# muscle.net
KiCad netlist of a schematic drawn in EAGLE
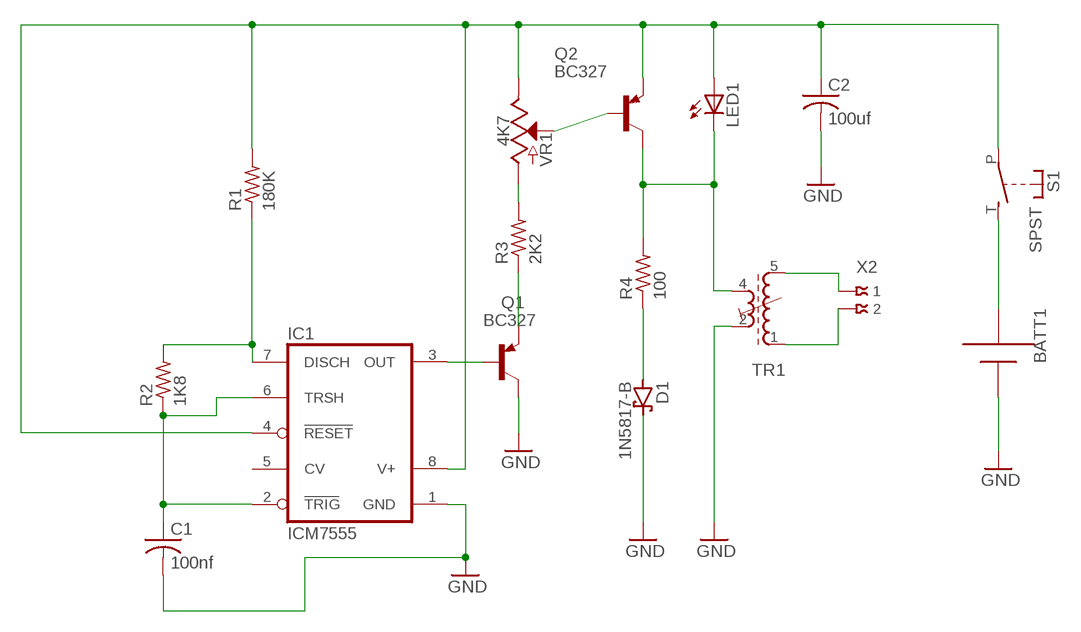
[diagram p0: schematic, sheet 1]

(export (version "E")
  (design (tool "Eeschema 10.0.6"))
  (components
    (comp (ref "BATT1")
      (value "AAA")
      (footprint "eagle-import:12BH412")
      (fields (field (name "MF") "BULGIN") (field (name "MPN") "BX0034"))
      (libsource (lib "eagle-import") (part "AAA"))
    )
    (comp (ref "C1")
      (value "100nf")
      (footprint "eagle-import:C025-024X044")
      (fields (field (name "MF") "AVX") (field (name "MPN") "12065C104KAT2A"))
      (libsource (lib "eagle-import") (part "C-US025-024X044"))
    )
    (comp (ref "C2")
      (value "100uf")
      (footprint "eagle-import:C025-024X044")
      (fields (field (name "MF") "KEMET") (field (name "MPN") "C1210C107M9PACTU"))
      (libsource (lib "eagle-import") (part "C-US025-024X044"))
    )
    (comp (ref "D1")
      (value "1N5817-B")
      (footprint "eagle-import:DO41-7.6")
      (fields (field (name "MF") "ON SEMICONDUCTOR") (field (name "MPN") "1N5817G"))
      (libsource (lib "eagle-import") (part "1N5817-B"))
    )
    (comp (ref "IC1")
      (value "ICM7555")
      (footprint "eagle-import:DIL08")
      (fields
        (field (name "MF") "MAXIM")
        (field (name "MPN") "ICM7555IPA+")
        (field (name "MF_1") "RENESAS")
        (field (name "MPN_1") "ICM7555IPAZ")
      )
      (libsource (lib "eagle-import") (part "ICM7555"))
    )
    (comp (ref "LED1")
      (value "LED3MM")
      (footprint "eagle-import:LED3MM")
      (fields (field (name "MF") "KINGBRIGHT") (field (name "MPN") "L-424IDT"))
      (libsource (lib "eagle-import") (part "LED3MM"))
    )
    (comp (ref "Q1")
      (value "BC327")
      (footprint "eagle-import:TO92")
      (libsource (lib "eagle-import") (part "BC327"))
    )
    (comp (ref "Q2")
      (value "BC327")
      (footprint "eagle-import:TO92")
      (libsource (lib "eagle-import") (part "BC327"))
    )
    (comp (ref "R1")
      (value "180K")
      (footprint "eagle-import:0204V")
      (libsource (lib "eagle-import") (part "R-US_0204/2V"))
    )
    (comp (ref "R2")
      (value "1K8")
      (footprint "eagle-import:0204V")
      (libsource (lib "eagle-import") (part "R-US_0204/2V"))
    )
    (comp (ref "R3")
      (value "2K2")
      (footprint "eagle-import:0204V")
      (libsource (lib "eagle-import") (part "R-US_0204/2V"))
    )
    (comp (ref "R4")
      (value "100")
      (footprint "eagle-import:0204V")
      (libsource (lib "eagle-import") (part "R-US_0204/2V"))
    )
    (comp (ref "S1")
      (value "SPST")
      (footprint "eagle-import:JUDCOSPST")
      (libsource (lib "eagle-import") (part "SPST"))
    )
    (comp (ref "TR1")
      (value "71-4-1524")
      (footprint "eagle-import:71-5")
      (libsource (lib "eagle-import") (part "71-4-1524"))
    )
    (comp (ref "VR1")
      (value "4K7")
      (footprint "eagle-import:SLIDER-SMALL")
      (libsource (lib "eagle-import") (part "POTENTIOMETER_SLIDE-20MM-1/10W-20%"))
    )
    (comp (ref "X2")
      (value "009177002")
      (footprint "eagle-import:009177002")
      (fields (field (name "MPN") "009177002001006"))
      (libsource (lib "eagle-import") (part "00917?0027"))
    )
  )
  (nets
    (net (code "1") (name "GND") (class "Default")
      (node (ref "BATT1") (pin "+") (pinfunction "+_+") (pintype "bidirectional"))
      (node (ref "C1") (pin "2") (pinfunction "2_2") (pintype "passive"))
      (node (ref "C2") (pin "2") (pinfunction "2_2") (pintype "passive"))
      (node (ref "D1") (pin "C") (pinfunction "C_C") (pintype "passive"))
      (node (ref "IC1") (pin "1") (pinfunction "GND_1") (pintype "power_in"))
      (node (ref "Q1") (pin "3") (pinfunction "C_3") (pintype "passive"))
      (node (ref "TR1") (pin "2") (pinfunction "A2_2") (pintype "passive"))
    )
    (net (code "2") (name "Net-(D1-PadA)") (class "Default")
      (node (ref "D1") (pin "A") (pinfunction "A_A") (pintype "passive"))
      (node (ref "R4") (pin "1") (pinfunction "1_1") (pintype "passive"))
    )
    (net (code "3") (name "Net-(IC1-DISCH)") (class "Default")
      (node (ref "IC1") (pin "7") (pinfunction "DISCH_7") (pintype "input"))
      (node (ref "R1") (pin "1") (pinfunction "1_1") (pintype "passive"))
      (node (ref "R2") (pin "2") (pinfunction "2_2") (pintype "passive"))
    )
    (net (code "4") (name "Net-(IC1-OUT)") (class "Default")
      (node (ref "IC1") (pin "3") (pinfunction "OUT_3") (pintype "output"))
      (node (ref "Q1") (pin "2") (pinfunction "B_2") (pintype "passive"))
    )
    (net (code "5") (name "Net-(IC1-RESET)") (class "Default")
      (node (ref "C2") (pin "1") (pinfunction "1_1") (pintype "passive"))
      (node (ref "IC1") (pin "4") (pinfunction "RESET_4") (pintype "input"))
      (node (ref "IC1") (pin "8") (pinfunction "V+_8") (pintype "power_in"))
      (node (ref "LED1") (pin "A") (pinfunction "A_A") (pintype "passive"))
      (node (ref "Q2") (pin "1") (pinfunction "E_1") (pintype "passive"))
      (node (ref "R1") (pin "2") (pinfunction "2_2") (pintype "passive"))
      (node (ref "S1") (pin "P") (pinfunction "P_P") (pintype "passive"))
      (node (ref "VR1") (pin "TOP") (pinfunction "E_TOP") (pintype "passive"))
    )
    (net (code "6") (name "Net-(IC1-TRIG)") (class "Default")
      (node (ref "C1") (pin "1") (pinfunction "1_1") (pintype "passive"))
      (node (ref "IC1") (pin "2") (pinfunction "TRIG_2") (pintype "bidirectional"))
      (node (ref "IC1") (pin "6") (pinfunction "TRSH_6") (pintype "input"))
      (node (ref "R2") (pin "1") (pinfunction "1_1") (pintype "passive"))
    )
    (net (code "7") (name "Net-(LED1-C)") (class "Default")
      (node (ref "LED1") (pin "K") (pinfunction "C_K") (pintype "passive"))
      (node (ref "Q2") (pin "3") (pinfunction "C_3") (pintype "passive"))
      (node (ref "R4") (pin "2") (pinfunction "2_2") (pintype "passive"))
      (node (ref "TR1") (pin "4") (pinfunction "E2_4") (pintype "passive"))
    )
    (net (code "8") (name "Net-(Q1-E)") (class "Default")
      (node (ref "Q1") (pin "1") (pinfunction "E_1") (pintype "passive"))
      (node (ref "R3") (pin "1") (pinfunction "1_1") (pintype "passive"))
    )
    (net (code "9") (name "Net-(Q2-B)") (class "Default")
      (node (ref "Q2") (pin "2") (pinfunction "B_2") (pintype "passive"))
      (node (ref "VR1") (pin "WIPER") (pinfunction "S_WIPER") (pintype "passive"))
    )
    (net (code "10") (name "Net-(S1-S)") (class "Default")
      (node (ref "BATT1") (pin "-") (pinfunction "-_-") (pintype "bidirectional"))
      (node (ref "S1") (pin "T") (pinfunction "S_T") (pintype "passive"))
    )
    (net (code "11") (name "Net-(TR1A-A1)") (class "Default")
      (node (ref "TR1") (pin "1") (pinfunction "A1_1") (pintype "passive"))
      (node (ref "X2") (pin "2") (pinfunction "2_2") (pintype "passive"))
    )
    (net (code "12") (name "Net-(TR1A-E1)") (class "Default")
      (node (ref "TR1") (pin "5") (pinfunction "E1_5") (pintype "passive"))
      (node (ref "X2") (pin "1") (pinfunction "1_1") (pintype "passive"))
    )
    (net (code "13") (name "Net-(VR1-A)") (class "Default")
      (node (ref "R3") (pin "2") (pinfunction "2_2") (pintype "passive"))
      (node (ref "VR1") (pin "BOTTOM") (pinfunction "A_BOTTOM") (pintype "passive"))
    )
    (net (code "14") (name "unconnected-(IC1-CV-Pad5)") (class "Default")
      (node (ref "IC1") (pin "5") (pinfunction "CV_5") (pintype "passive"))
    )
  )
)
